# flute.net
KiCad netlist of a schematic drawn in EAGLE
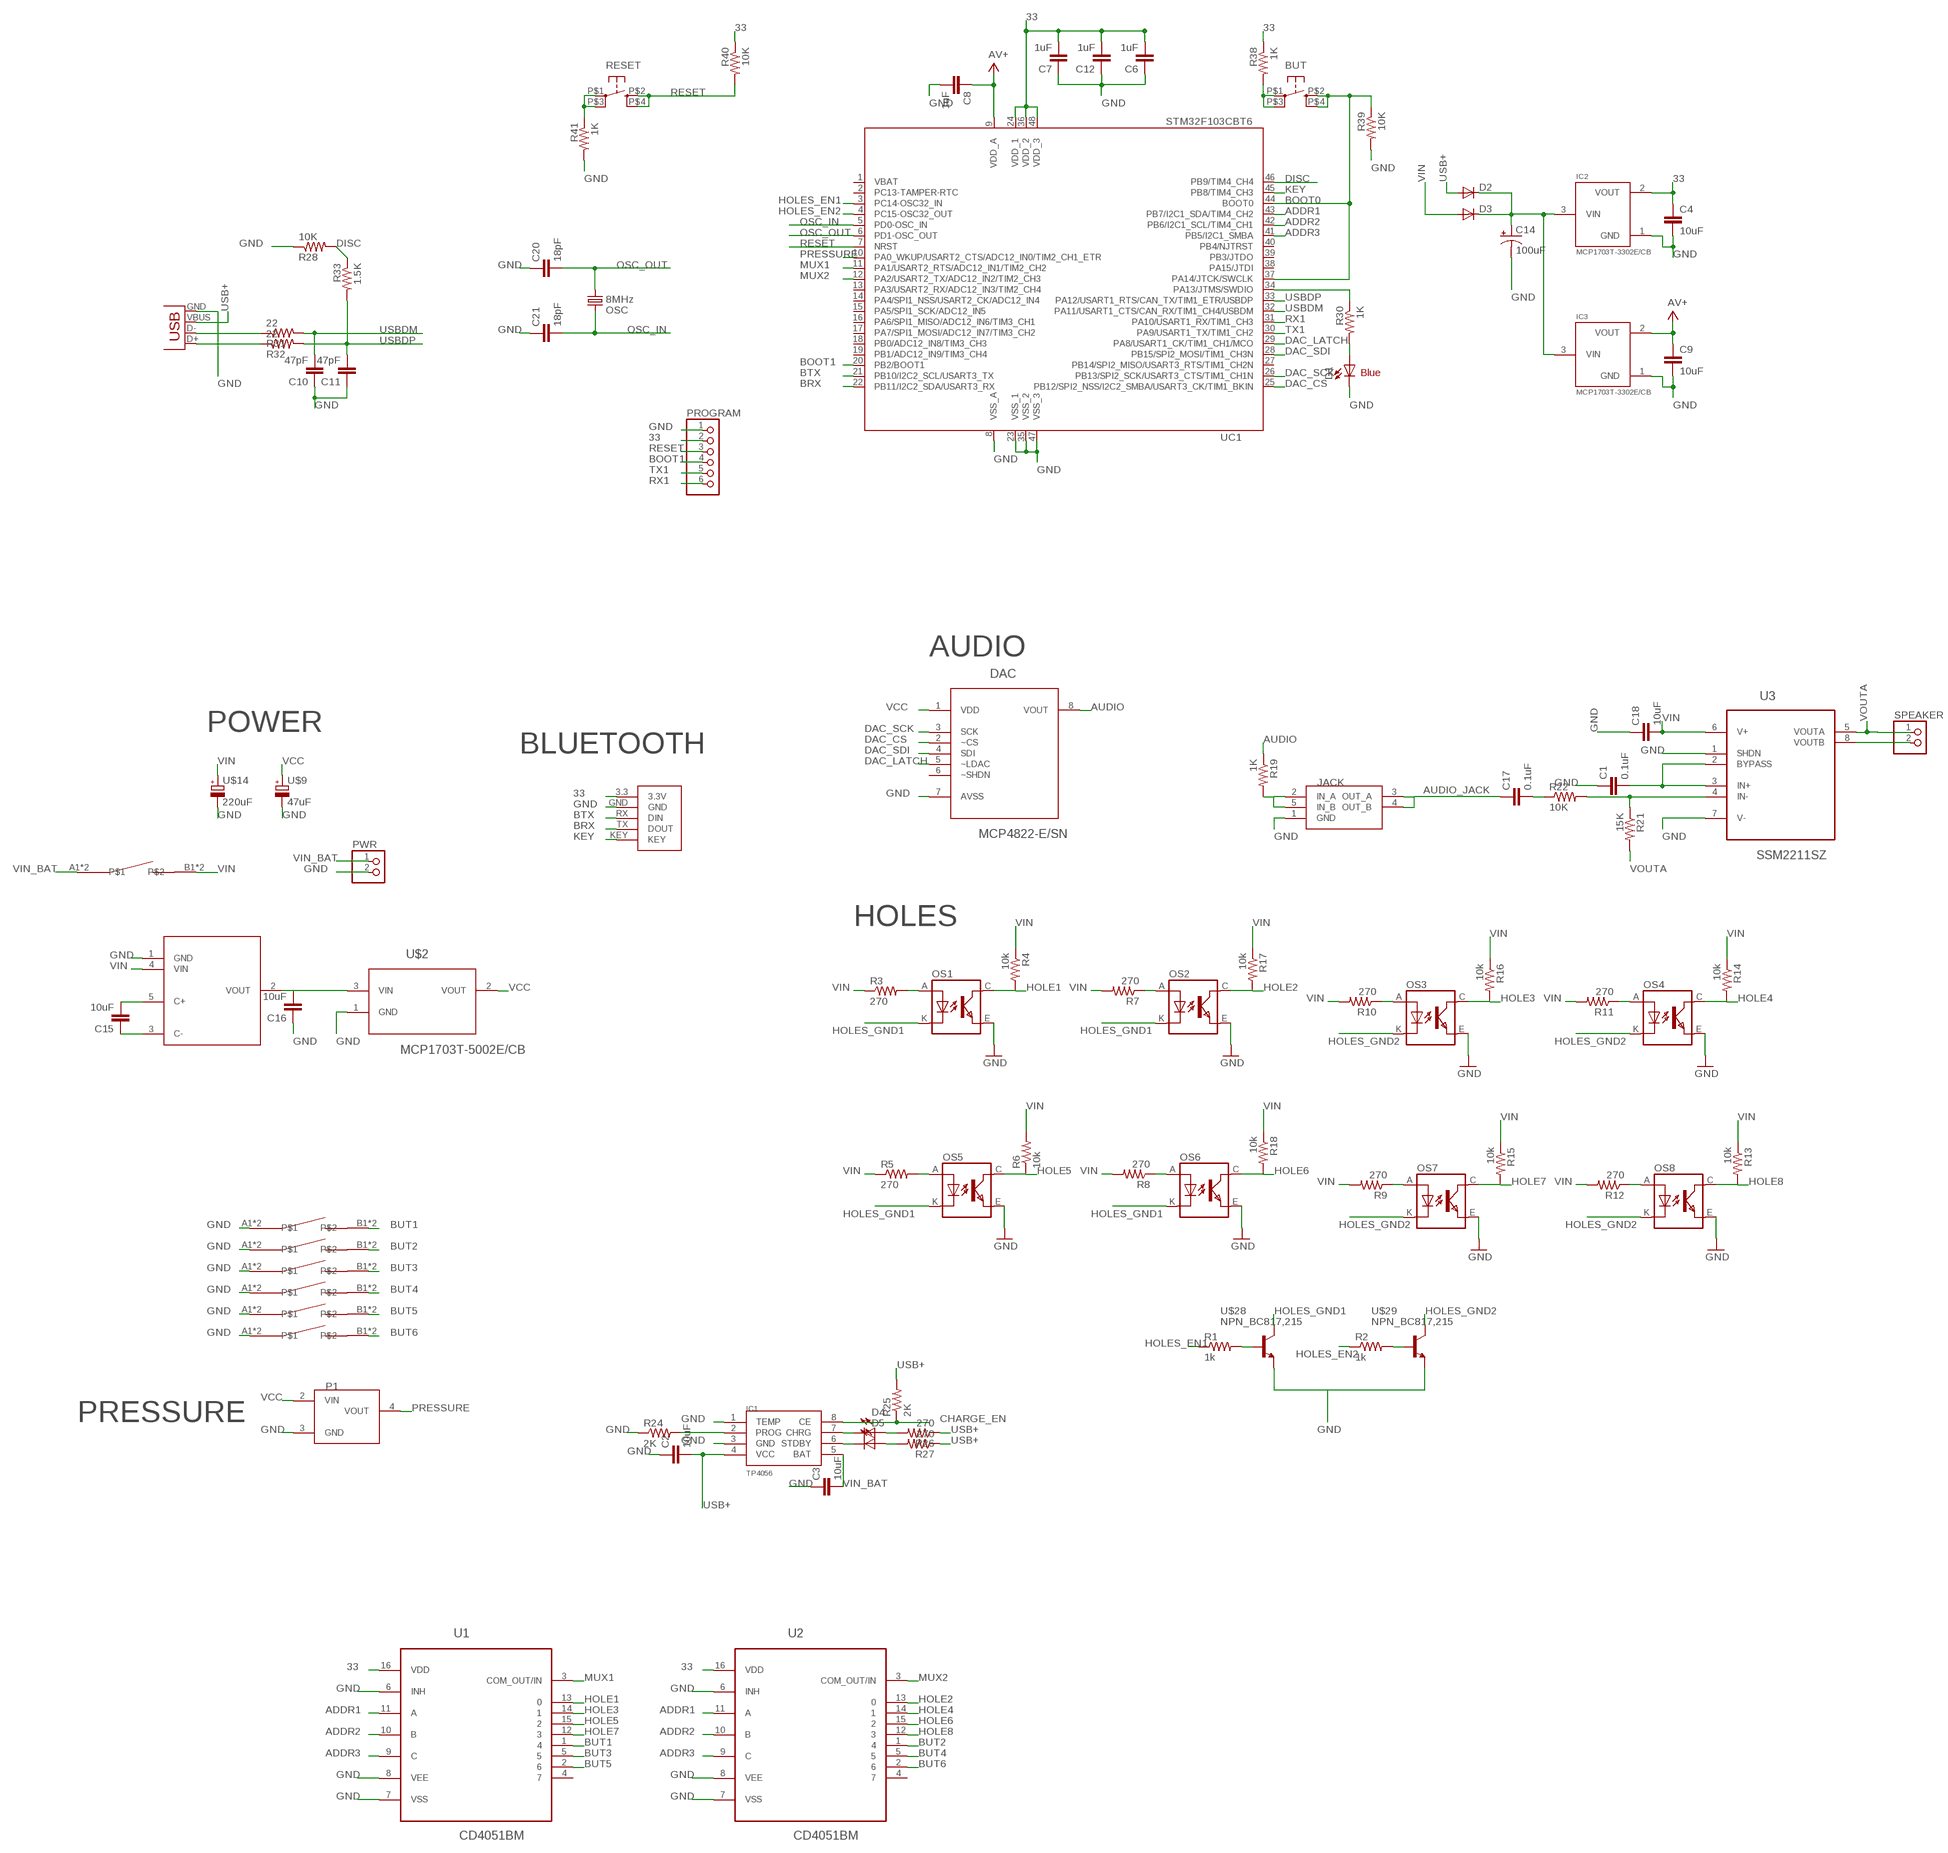
[diagram p0: schematic, sheet 1]

(export (version "E")
  (design (tool "Eeschema 10.0.6"))
  (components
    (comp (ref "BUT")
      (value "KMR211GLFS")
      (footprint "eagle-import:PUSHBUTTON-KMR241GLFS")
      (libsource (lib "eagle-import") (part "BUTTON-KMR241GLFS"))
    )
    (comp (ref "C1")
      (value "0.1uF")
      (footprint "eagle-import:0805")
      (libsource (lib "eagle-import") (part "CAP0805"))
    )
    (comp (ref "C2")
      (value "10uF")
      (footprint "eagle-import:0805")
      (libsource (lib "eagle-import") (part "CAP0805"))
    )
    (comp (ref "C3")
      (value "10uF")
      (footprint "eagle-import:0805")
      (libsource (lib "eagle-import") (part "CAP0805"))
    )
    (comp (ref "C4")
      (value "10uF")
      (footprint "eagle-import:0805")
      (libsource (lib "eagle-import") (part "SparkFun2_CAP0805"))
    )
    (comp (ref "C6")
      (value "1uF")
      (footprint "eagle-import:0805")
      (libsource (lib "eagle-import") (part "CAP0805"))
    )
    (comp (ref "C7")
      (value "1uF")
      (footprint "eagle-import:0805")
      (libsource (lib "eagle-import") (part "CAP0805"))
    )
    (comp (ref "C8")
      (value "1uF")
      (footprint "eagle-import:0805")
      (libsource (lib "eagle-import") (part "CAP0805"))
    )
    (comp (ref "C9")
      (value "10uF")
      (footprint "eagle-import:0805")
      (libsource (lib "eagle-import") (part "SparkFun2_CAP0805"))
    )
    (comp (ref "C10")
      (value "47pF")
      (footprint "eagle-import:0805")
      (libsource (lib "eagle-import") (part "CAP0805"))
    )
    (comp (ref "C11")
      (value "47pF")
      (footprint "eagle-import:0805")
      (libsource (lib "eagle-import") (part "CAP0805"))
    )
    (comp (ref "C12")
      (value "1uF")
      (footprint "eagle-import:0805")
      (libsource (lib "eagle-import") (part "CAP0805"))
    )
    (comp (ref "C14")
      (value "100uF")
      (footprint "eagle-import:EIA3216")
      (libsource (lib "eagle-import") (part "CAP_POL1206"))
    )
    (comp (ref "C15")
      (value "10uF")
      (footprint "eagle-import:0805")
      (libsource (lib "eagle-import") (part "CAP0805"))
    )
    (comp (ref "C16")
      (value "10uF")
      (footprint "eagle-import:0805")
      (libsource (lib "eagle-import") (part "CAP0805"))
    )
    (comp (ref "C17")
      (value "0.1uF")
      (footprint "eagle-import:0805")
      (libsource (lib "eagle-import") (part "CAP0805"))
    )
    (comp (ref "C18")
      (value "10uF")
      (footprint "eagle-import:0805")
      (libsource (lib "eagle-import") (part "CAP0805"))
    )
    (comp (ref "C20")
      (value "18pF")
      (footprint "eagle-import:0805")
      (libsource (lib "eagle-import") (part "CAP0805"))
    )
    (comp (ref "C21")
      (value "18pF")
      (footprint "eagle-import:0805")
      (libsource (lib "eagle-import") (part "CAP0805"))
    )
    (comp (ref "D1")
      (value "Blue")
      (footprint "eagle-import:LED-1206")
      (libsource (lib "eagle-import") (part "LED1206"))
    )
    (comp (ref "D2")
      (value "DIODESOD")
      (footprint "eagle-import:SOD-323")
      (libsource (lib "eagle-import") (part "DIODESOD"))
    )
    (comp (ref "D3")
      (value "DIODESOD")
      (footprint "eagle-import:SOD-323")
      (libsource (lib "eagle-import") (part "DIODESOD"))
    )
    (comp (ref "D4")
      (value "Red")
      (footprint "eagle-import:LED-1206")
      (libsource (lib "eagle-import") (part "LED1206"))
    )
    (comp (ref "D5")
      (value "Green")
      (footprint "eagle-import:LED-1206")
      (libsource (lib "eagle-import") (part "LED1206"))
    )
    (comp (ref "DAC")
      (value "MCP4822-E/SN")
      (footprint "eagle-import:SOIC8-N_MC")
      (libsource (lib "eagle-import") (part "MCP4822-E/SN"))
    )
    (comp (ref "IC1")
      (value "TP4056")
      (footprint "eagle-import:SOP-8")
      (libsource (lib "eagle-import") (part "TP4056"))
    )
    (comp (ref "IC2")
      (value "MCP1703T-3302E/CB")
      (footprint "eagle-import:SOT23")
      (libsource (lib "eagle-import") (part "MCP1700T"))
    )
    (comp (ref "IC3")
      (value "MCP1703T-3302E/CB")
      (footprint "eagle-import:SOT23")
      (libsource (lib "eagle-import") (part "MCP1700T"))
    )
    (comp (ref "JACK")
      (value "JACK")
      (footprint "eagle-import:3F07")
      (libsource (lib "eagle-import") (part "JACK"))
    )
    (comp (ref "OS1")
      (value "TCRT5000")
      (footprint "eagle-import:TCRT5000")
      (libsource (lib "eagle-import") (part "TCRT5000"))
    )
    (comp (ref "OS2")
      (value "TCRT5000")
      (footprint "eagle-import:TCRT5000")
      (libsource (lib "eagle-import") (part "TCRT5000"))
    )
    (comp (ref "OS3")
      (value "TCRT5000")
      (footprint "eagle-import:TCRT5000")
      (libsource (lib "eagle-import") (part "TCRT5000"))
    )
    (comp (ref "OS4")
      (value "TCRT5000")
      (footprint "eagle-import:TCRT5000")
      (libsource (lib "eagle-import") (part "TCRT5000"))
    )
    (comp (ref "OS5")
      (value "TCRT5000")
      (footprint "eagle-import:TCRT5000")
      (libsource (lib "eagle-import") (part "TCRT5000"))
    )
    (comp (ref "OS6")
      (value "TCRT5000")
      (footprint "eagle-import:TCRT5000")
      (libsource (lib "eagle-import") (part "TCRT5000"))
    )
    (comp (ref "OS7")
      (value "TCRT5000")
      (footprint "eagle-import:TCRT5000")
      (libsource (lib "eagle-import") (part "TCRT5000"))
    )
    (comp (ref "OS8")
      (value "TCRT5000")
      (footprint "eagle-import:TCRT5000")
      (libsource (lib "eagle-import") (part "TCRT5000"))
    )
    (comp (ref "OSC")
      (value "8MHz")
      (footprint "eagle-import:CRYSTAL-SMD-5X3")
      (libsource (lib "eagle-import") (part "CRYSTAL5X3"))
    )
    (comp (ref "P1")
      (value "PRESSURE_SENSOR")
      (footprint "eagle-import:MPXV5050GP")
      (libsource (lib "eagle-import") (part "PRESSURE_SENSOR"))
    )
    (comp (ref "PROGRAM")
      (value "CONNEC_1X066PADS")
      (footprint "eagle-import:6PADS")
      (libsource (lib "eagle-import") (part "CONNEC_1X066PADS"))
    )
    (comp (ref "PWR")
      (value "CONNEC_1X02BASIC")
      (footprint "eagle-import:CONNEC_1X02")
      (libsource (lib "eagle-import") (part "CONNEC_1X02BASIC"))
    )
    (comp (ref "R1")
      (value "1k")
      (footprint "eagle-import:0805")
      (libsource (lib "eagle-import") (part "RESISTOR0805-RES"))
    )
    (comp (ref "R2")
      (value "1k")
      (footprint "eagle-import:0805")
      (libsource (lib "eagle-import") (part "RESISTOR0805-RES"))
    )
    (comp (ref "R3")
      (value "270")
      (footprint "eagle-import:0805")
      (libsource (lib "eagle-import") (part "RESISTOR0805-RES"))
    )
    (comp (ref "R4")
      (value "10k")
      (footprint "eagle-import:0805")
      (libsource (lib "eagle-import") (part "RESISTOR0805-RES"))
    )
    (comp (ref "R5")
      (value "270")
      (footprint "eagle-import:0805")
      (libsource (lib "eagle-import") (part "RESISTOR0805-RES"))
    )
    (comp (ref "R6")
      (value "10k")
      (footprint "eagle-import:0805")
      (libsource (lib "eagle-import") (part "RESISTOR0805-RES"))
    )
    (comp (ref "R7")
      (value "270")
      (footprint "eagle-import:0805")
      (libsource (lib "eagle-import") (part "RESISTOR0805-RES"))
    )
    (comp (ref "R8")
      (value "270")
      (footprint "eagle-import:0805")
      (libsource (lib "eagle-import") (part "RESISTOR0805-RES"))
    )
    (comp (ref "R9")
      (value "270")
      (footprint "eagle-import:0805")
      (libsource (lib "eagle-import") (part "RESISTOR0805-RES"))
    )
    (comp (ref "R10")
      (value "270")
      (footprint "eagle-import:0805")
      (libsource (lib "eagle-import") (part "RESISTOR0805-RES"))
    )
    (comp (ref "R11")
      (value "270")
      (footprint "eagle-import:0805")
      (libsource (lib "eagle-import") (part "RESISTOR0805-RES"))
    )
    (comp (ref "R12")
      (value "270")
      (footprint "eagle-import:0805")
      (libsource (lib "eagle-import") (part "RESISTOR0805-RES"))
    )
    (comp (ref "R13")
      (value "10k")
      (footprint "eagle-import:0805")
      (libsource (lib "eagle-import") (part "RESISTOR0805-RES"))
    )
    (comp (ref "R14")
      (value "10k")
      (footprint "eagle-import:0805")
      (libsource (lib "eagle-import") (part "RESISTOR0805-RES"))
    )
    (comp (ref "R15")
      (value "10k")
      (footprint "eagle-import:0805")
      (libsource (lib "eagle-import") (part "RESISTOR0805-RES"))
    )
    (comp (ref "R16")
      (value "10k")
      (footprint "eagle-import:0805")
      (libsource (lib "eagle-import") (part "RESISTOR0805-RES"))
    )
    (comp (ref "R17")
      (value "10k")
      (footprint "eagle-import:0805")
      (libsource (lib "eagle-import") (part "RESISTOR0805-RES"))
    )
    (comp (ref "R18")
      (value "10k")
      (footprint "eagle-import:0805")
      (libsource (lib "eagle-import") (part "RESISTOR0805-RES"))
    )
    (comp (ref "R19")
      (value "1K")
      (footprint "eagle-import:0805")
      (libsource (lib "eagle-import") (part "RESISTOR0805-RES"))
    )
    (comp (ref "R21")
      (value "15K")
      (footprint "eagle-import:0805")
      (libsource (lib "eagle-import") (part "RESISTOR0805-RES"))
    )
    (comp (ref "R22")
      (value "10K")
      (footprint "eagle-import:0805")
      (libsource (lib "eagle-import") (part "RESISTOR0805-RES"))
    )
    (comp (ref "R24")
      (value "2K")
      (footprint "eagle-import:0805")
      (libsource (lib "eagle-import") (part "RESISTOR0805-RES"))
    )
    (comp (ref "R25")
      (value "2K")
      (footprint "eagle-import:0805")
      (libsource (lib "eagle-import") (part "RESISTOR0805-RES"))
    )
    (comp (ref "R26")
      (value "270")
      (footprint "eagle-import:0805")
      (libsource (lib "eagle-import") (part "RESISTOR0805-RES"))
    )
    (comp (ref "R27")
      (value "270")
      (footprint "eagle-import:0805")
      (libsource (lib "eagle-import") (part "RESISTOR0805-RES"))
    )
    (comp (ref "R28")
      (value "10K")
      (footprint "eagle-import:0805")
      (libsource (lib "eagle-import") (part "RESISTOR0805-RES"))
    )
    (comp (ref "R30")
      (value "1K")
      (footprint "eagle-import:0805")
      (libsource (lib "eagle-import") (part "RESISTOR0805-RES"))
    )
    (comp (ref "R31")
      (value "22")
      (footprint "eagle-import:0805")
      (libsource (lib "eagle-import") (part "RESISTOR0805-RES"))
    )
    (comp (ref "R32")
      (value "22")
      (footprint "eagle-import:0805")
      (libsource (lib "eagle-import") (part "RESISTOR0805-RES"))
    )
    (comp (ref "R33")
      (value "1.5K")
      (footprint "eagle-import:0805")
      (libsource (lib "eagle-import") (part "RESISTOR0805-RES"))
    )
    (comp (ref "R38")
      (value "1K")
      (footprint "eagle-import:0805")
      (libsource (lib "eagle-import") (part "RESISTOR0805-RES"))
    )
    (comp (ref "R39")
      (value "10K")
      (footprint "eagle-import:0805")
      (libsource (lib "eagle-import") (part "RESISTOR0805-RES"))
    )
    (comp (ref "R40")
      (value "10K")
      (footprint "eagle-import:0805")
      (libsource (lib "eagle-import") (part "RESISTOR0805-RES"))
    )
    (comp (ref "R41")
      (value "1K")
      (footprint "eagle-import:0805")
      (libsource (lib "eagle-import") (part "RESISTOR0805-RES"))
    )
    (comp (ref "RESET")
      (value "KMR211GLFS")
      (footprint "eagle-import:PUSHBUTTON-KMR241GLFS")
      (libsource (lib "eagle-import") (part "BUTTON-KMR241GLFS"))
    )
    (comp (ref "SPEAKER")
      (value "CONNEC_1X02BASIC")
      (footprint "eagle-import:CONNEC_1X02")
      (libsource (lib "eagle-import") (part "CONNEC_1X02BASIC"))
    )
    (comp (ref "U$1")
      (value "MAX1683")
      (footprint "eagle-import:SOT23-5")
      (libsource (lib "eagle-import") (part "MAX1683"))
    )
    (comp (ref "U$2")
      (value "MCP1703T-5002E/CB")
      (footprint "eagle-import:SOT95P300X145-3N")
      (libsource (lib "eagle-import") (part "MCP1703T-5002E/CB"))
    )
    (comp (ref "U$9")
      (value "47uF")
      (footprint "eagle-import:PANASONIC_D")
      (libsource (lib "eagle-import") (part "CPOL_EUPANASONIC_D"))
    )
    (comp (ref "U$14")
      (value "220uF")
      (footprint "eagle-import:PANASONIC_D8")
      (libsource (lib "eagle-import") (part "CPOL_EUPANASONIC_D8"))
    )
    (comp (ref "U$16")
      (value "SWITCHKCD11")
      (footprint "eagle-import:KCD11")
      (libsource (lib "eagle-import") (part "SWITCHKCD11"))
    )
    (comp (ref "U$18")
      (value "SWITCH6X6X10")
      (footprint "eagle-import:SWITCH_6X6X10")
      (libsource (lib "eagle-import") (part "SWITCH6X6X10"))
    )
    (comp (ref "U$19")
      (value "SWITCH6X6X10")
      (footprint "eagle-import:SWITCH_6X6X10")
      (libsource (lib "eagle-import") (part "SWITCH6X6X10"))
    )
    (comp (ref "U$20")
      (value "SWITCH6X6X10")
      (footprint "eagle-import:SWITCH_6X6X10")
      (libsource (lib "eagle-import") (part "SWITCH6X6X10"))
    )
    (comp (ref "U$21")
      (value "SWITCH6X6X10")
      (footprint "eagle-import:SWITCH_6X6X10")
      (libsource (lib "eagle-import") (part "SWITCH6X6X10"))
    )
    (comp (ref "U$22")
      (value "SWITCH6X6X10")
      (footprint "eagle-import:SWITCH_6X6X10")
      (libsource (lib "eagle-import") (part "SWITCH6X6X10"))
    )
    (comp (ref "U$23")
      (value "SWITCH6X6X10")
      (footprint "eagle-import:SWITCH_6X6X10")
      (libsource (lib "eagle-import") (part "SWITCH6X6X10"))
    )
    (comp (ref "U$24")
      (value "HC05")
      (footprint "eagle-import:HC-05")
      (libsource (lib "eagle-import") (part "HC05"))
    )
    (comp (ref "U$28")
      (value "NPN_BC817,215")
      (footprint "eagle-import:SOT-23")
      (libsource (lib "eagle-import") (part "NPN_BC817,215"))
    )
    (comp (ref "U$29")
      (value "NPN_BC817,215")
      (footprint "eagle-import:SOT-23")
      (libsource (lib "eagle-import") (part "NPN_BC817,215"))
    )
    (comp (ref "U1")
      (value "CD4051BM")
      (footprint "eagle-import:SOIC127P600X175-16N")
      (libsource (lib "eagle-import") (part "CD4051BM"))
    )
    (comp (ref "U2")
      (value "CD4051BM")
      (footprint "eagle-import:SOIC127P600X175-16N")
      (libsource (lib "eagle-import") (part "CD4051BM"))
    )
    (comp (ref "U3")
      (value "SSM2211SZ")
      (footprint "eagle-import:SOIC127P600X175-8N")
      (libsource (lib "eagle-import") (part "SSM2211SZ"))
    )
    (comp (ref "UC1")
      (value "STM32F103CBT6")
      (footprint "eagle-import:LQFP48")
      (libsource (lib "eagle-import") (part "STM32F103CB"))
    )
    (comp (ref "X1")
      (value "USB-MINIB")
      (footprint "eagle-import:USB-MINIB")
      (libsource (lib "eagle-import") (part "USBSMD"))
    )
  )
  (nets
    (net (code "1") (name "/33") (class "Default")
      (node (ref "C12") (pin "2") (pinfunction "2_2") (pintype "passive"))
      (node (ref "C4") (pin "1") (pinfunction "1_1") (pintype "passive"))
      (node (ref "C6") (pin "2") (pinfunction "2_2") (pintype "passive"))
      (node (ref "C7") (pin "2") (pinfunction "2_2") (pintype "passive"))
      (node (ref "IC2") (pin "2") (pinfunction "VOUT_2") (pintype "bidirectional"))
      (node (ref "PROGRAM") (pin "2") (pinfunction "2_2") (pintype "passive"))
      (node (ref "R38") (pin "1") (pinfunction "1_1") (pintype "passive"))
      (node (ref "R40") (pin "1") (pinfunction "1_1") (pintype "passive"))
      (node (ref "U$24") (pin "3.3") (pinfunction "3.3V_3.3") (pintype "bidirectional"))
      (node (ref "U1") (pin "16") (pinfunction "VDD_16") (pintype "input"))
      (node (ref "U2") (pin "16") (pinfunction "VDD_16") (pintype "input"))
      (node (ref "UC1") (pin "24") (pinfunction "VDD_1_24") (pintype "power_in"))
      (node (ref "UC1") (pin "36") (pinfunction "VDD_2_36") (pintype "power_in"))
      (node (ref "UC1") (pin "48") (pinfunction "VDD_3_48") (pintype "power_in"))
    )
    (net (code "2") (name "/ADDR1") (class "Default")
      (node (ref "U1") (pin "11") (pinfunction "A_11") (pintype "input"))
      (node (ref "U2") (pin "11") (pinfunction "A_11") (pintype "input"))
      (node (ref "UC1") (pin "43") (pinfunction "PB7/I2C1_SDA/TIM4_CH2_43") (pintype "bidirectional"))
    )
    (net (code "3") (name "/ADDR2") (class "Default")
      (node (ref "U1") (pin "10") (pinfunction "B_10") (pintype "input"))
      (node (ref "U2") (pin "10") (pinfunction "B_10") (pintype "input"))
      (node (ref "UC1") (pin "42") (pinfunction "PB6/I2C1_SCL/TIM4_CH1_42") (pintype "input"))
    )
    (net (code "4") (name "/ADDR3") (class "Default")
      (node (ref "U1") (pin "9") (pinfunction "C_9") (pintype "bidirectional"))
      (node (ref "U2") (pin "9") (pinfunction "C_9") (pintype "bidirectional"))
      (node (ref "UC1") (pin "41") (pinfunction "PB5/I2C1_SMBA_41") (pintype "input"))
    )
    (net (code "5") (name "/AUDIO") (class "Default")
      (node (ref "DAC") (pin "8") (pinfunction "VOUT_8") (pintype "output"))
      (node (ref "R19") (pin "1") (pinfunction "1_1") (pintype "passive"))
    )
    (net (code "6") (name "/AUDIO_JACK") (class "Default")
      (node (ref "C17") (pin "1") (pinfunction "1_1") (pintype "passive"))
      (node (ref "JACK") (pin "3") (pinfunction "OUT_A_3") (pintype "bidirectional"))
      (node (ref "JACK") (pin "4") (pinfunction "OUT_B_4") (pintype "bidirectional"))
    )
    (net (code "7") (name "/BOOT1") (class "Default")
      (node (ref "PROGRAM") (pin "4") (pinfunction "4_4") (pintype "passive"))
      (node (ref "UC1") (pin "20") (pinfunction "PB2/BOOT1_20") (pintype "bidirectional"))
    )
    (net (code "8") (name "/BRX") (class "Default")
      (node (ref "U$24") (pin "TX") (pinfunction "DOUT_TX") (pintype "bidirectional"))
      (node (ref "UC1") (pin "22") (pinfunction "PB11/I2C2_SDA/USART3_RX_22") (pintype "input"))
    )
    (net (code "9") (name "/BTX") (class "Default")
      (node (ref "U$24") (pin "RX") (pinfunction "DIN_RX") (pintype "bidirectional"))
      (node (ref "UC1") (pin "21") (pinfunction "PB10/I2C2_SCL/USART3_TX_21") (pintype "input"))
    )
    (net (code "10") (name "/BUT1") (class "Default")
      (node (ref "U$18") (pin "B1") (pinfunction "P$2_B1") (pintype "bidirectional"))
      (node (ref "U$18") (pin "B2") (pinfunction "P$2_B2") (pintype "bidirectional"))
      (node (ref "U1") (pin "1") (pinfunction "4_1") (pintype "bidirectional"))
    )
    (net (code "11") (name "/BUT2") (class "Default")
      (node (ref "U$19") (pin "B1") (pinfunction "P$2_B1") (pintype "bidirectional"))
      (node (ref "U$19") (pin "B2") (pinfunction "P$2_B2") (pintype "bidirectional"))
      (node (ref "U2") (pin "1") (pinfunction "4_1") (pintype "bidirectional"))
    )
    (net (code "12") (name "/BUT3") (class "Default")
      (node (ref "U$20") (pin "B1") (pinfunction "P$2_B1") (pintype "bidirectional"))
      (node (ref "U$20") (pin "B2") (pinfunction "P$2_B2") (pintype "bidirectional"))
      (node (ref "U1") (pin "5") (pinfunction "5_5") (pintype "bidirectional"))
    )
    (net (code "13") (name "/BUT4") (class "Default")
      (node (ref "U$21") (pin "B1") (pinfunction "P$2_B1") (pintype "bidirectional"))
      (node (ref "U$21") (pin "B2") (pinfunction "P$2_B2") (pintype "bidirectional"))
      (node (ref "U2") (pin "5") (pinfunction "5_5") (pintype "bidirectional"))
    )
    (net (code "14") (name "/BUT5") (class "Default")
      (node (ref "U$22") (pin "B1") (pinfunction "P$2_B1") (pintype "bidirectional"))
      (node (ref "U$22") (pin "B2") (pinfunction "P$2_B2") (pintype "bidirectional"))
      (node (ref "U1") (pin "2") (pinfunction "6_2") (pintype "bidirectional"))
    )
    (net (code "15") (name "/BUT6") (class "Default")
      (node (ref "U$23") (pin "B1") (pinfunction "P$2_B1") (pintype "bidirectional"))
      (node (ref "U$23") (pin "B2") (pinfunction "P$2_B2") (pintype "bidirectional"))
      (node (ref "U2") (pin "2") (pinfunction "6_2") (pintype "bidirectional"))
    )
    (net (code "16") (name "/CHARGE_EN") (class "Default")
      (node (ref "IC1") (pin "8") (pinfunction "CE_8") (pintype "bidirectional"))
      (node (ref "R25") (pin "1") (pinfunction "1_1") (pintype "passive"))
    )
    (net (code "17") (name "/DAC_CS") (class "Default")
      (node (ref "DAC") (pin "2") (pinfunction "~{CS}_2") (pintype "input"))
      (node (ref "UC1") (pin "25") (pinfunction "PB12/SPI2_NSS/I2C2_SMBA/USART3_CK/TIM1_BKIN_25") (pintype "input"))
    )
    (net (code "18") (name "/DAC_LATCH") (class "Default")
      (node (ref "DAC") (pin "5") (pinfunction "~{LDAC}_5") (pintype "input"))
      (node (ref "UC1") (pin "29") (pinfunction "PA8/USART1_CK/TIM1_CH1/MCO_29") (pintype "bidirectional"))
    )
    (net (code "19") (name "/DAC_SCK") (class "Default")
      (node (ref "DAC") (pin "3") (pinfunction "SCK_3") (pintype "input"))
      (node (ref "UC1") (pin "26") (pinfunction "PB13/SPI2_SCK/USART3_CTS/TIM1_CH1N_26") (pintype "input"))
    )
    (net (code "20") (name "/DAC_SDI") (class "Default")
      (node (ref "DAC") (pin "4") (pinfunction "SDI_4") (pintype "input"))
      (node (ref "UC1") (pin "28") (pinfunction "PB15/SPI2_MOSI/TIM1_CH3N_28") (pintype "input"))
    )
    (net (code "21") (name "/DISC") (class "Default")
      (node (ref "R28") (pin "2") (pinfunction "2_2") (pintype "passive"))
      (node (ref "R33") (pin "1") (pinfunction "1_1") (pintype "passive"))
      (node (ref "UC1") (pin "46") (pinfunction "PB9/TIM4_CH4_46") (pintype "input"))
    )
    (net (code "22") (name "/HOLE1") (class "Default")
      (node (ref "OS1") (pin "C") (pinfunction "COLLECTOR_C") (pintype "passive"))
      (node (ref "R4") (pin "2") (pinfunction "2_2") (pintype "passive"))
      (node (ref "U1") (pin "13") (pinfunction "0_13") (pintype "bidirectional"))
    )
    (net (code "23") (name "/HOLE2") (class "Default")
      (node (ref "OS2") (pin "C") (pinfunction "COLLECTOR_C") (pintype "passive"))
      (node (ref "R17") (pin "2") (pinfunction "2_2") (pintype "passive"))
      (node (ref "U2") (pin "13") (pinfunction "0_13") (pintype "bidirectional"))
    )
    (net (code "24") (name "/HOLE3") (class "Default")
      (node (ref "OS3") (pin "C") (pinfunction "COLLECTOR_C") (pintype "passive"))
      (node (ref "R16") (pin "2") (pinfunction "2_2") (pintype "passive"))
      (node (ref "U1") (pin "14") (pinfunction "1_14") (pintype "bidirectional"))
    )
    (net (code "25") (name "/HOLE4") (class "Default")
      (node (ref "OS4") (pin "C") (pinfunction "COLLECTOR_C") (pintype "passive"))
      (node (ref "R14") (pin "2") (pinfunction "2_2") (pintype "passive"))
      (node (ref "U2") (pin "14") (pinfunction "1_14") (pintype "bidirectional"))
    )
    (net (code "26") (name "/HOLE5") (class "Default")
      (node (ref "OS5") (pin "C") (pinfunction "COLLECTOR_C") (pintype "passive"))
      (node (ref "R6") (pin "1") (pinfunction "1_1") (pintype "passive"))
      (node (ref "U1") (pin "15") (pinfunction "2_15") (pintype "bidirectional"))
    )
    (net (code "27") (name "/HOLE6") (class "Default")
      (node (ref "OS6") (pin "C") (pinfunction "COLLECTOR_C") (pintype "passive"))
      (node (ref "R18") (pin "2") (pinfunction "2_2") (pintype "passive"))
      (node (ref "U2") (pin "15") (pinfunction "2_15") (pintype "bidirectional"))
    )
    (net (code "28") (name "/HOLE7") (class "Default")
      (node (ref "OS7") (pin "C") (pinfunction "COLLECTOR_C") (pintype "passive"))
      (node (ref "R15") (pin "2") (pinfunction "2_2") (pintype "passive"))
      (node (ref "U1") (pin "12") (pinfunction "3_12") (pintype "bidirectional"))
    )
    (net (code "29") (name "/HOLE8") (class "Default")
      (node (ref "OS8") (pin "C") (pinfunction "COLLECTOR_C") (pintype "passive"))
      (node (ref "R13") (pin "2") (pinfunction "2_2") (pintype "passive"))
      (node (ref "U2") (pin "12") (pinfunction "3_12") (pintype "bidirectional"))
    )
    (net (code "30") (name "/HOLES_EN1") (class "Default")
      (node (ref "R1") (pin "1") (pinfunction "1_1") (pintype "passive"))
      (node (ref "UC1") (pin "3") (pinfunction "PC14-OSC32_IN_3") (pintype "input"))
    )
    (net (code "31") (name "/HOLES_EN2") (class "Default")
      (node (ref "R2") (pin "1") (pinfunction "1_1") (pintype "passive"))
      (node (ref "UC1") (pin "4") (pinfunction "PC15-OSC32_OUT_4") (pintype "input"))
    )
    (net (code "32") (name "/HOLES_GND1") (class "Default")
      (node (ref "OS1") (pin "K") (pinfunction "CATHODE_K") (pintype "passive"))
      (node (ref "OS2") (pin "K") (pinfunction "CATHODE_K") (pintype "passive"))
      (node (ref "OS5") (pin "K") (pinfunction "CATHODE_K") (pintype "passive"))
      (node (ref "OS6") (pin "K") (pinfunction "CATHODE_K") (pintype "passive"))
      (node (ref "U$28") (pin "3") (pinfunction "C_3") (pintype "passive"))
    )
    (net (code "33") (name "/HOLES_GND2") (class "Default")
      (node (ref "OS3") (pin "K") (pinfunction "CATHODE_K") (pintype "passive"))
      (node (ref "OS4") (pin "K") (pinfunction "CATHODE_K") (pintype "passive"))
      (node (ref "OS7") (pin "K") (pinfunction "CATHODE_K") (pintype "passive"))
      (node (ref "OS8") (pin "K") (pinfunction "CATHODE_K") (pintype "passive"))
      (node (ref "U$29") (pin "3") (pinfunction "C_3") (pintype "passive"))
    )
    (net (code "34") (name "/KEY") (class "Default")
      (node (ref "U$24") (pin "KEY") (pinfunction "KEY_KEY") (pintype "bidirectional"))
      (node (ref "UC1") (pin "45") (pinfunction "PB8/TIM4_CH3_45") (pintype "bidirectional"))
    )
    (net (code "35") (name "/MUX1") (class "Default")
      (node (ref "U1") (pin "3") (pinfunction "COM_OUT/IN_3") (pintype "bidirectional"))
      (node (ref "UC1") (pin "11") (pinfunction "PA1/USART2_RTS/ADC12_IN1/TIM2_CH2_11") (pintype "bidirectional"))
    )
    (net (code "36") (name "/MUX2") (class "Default")
      (node (ref "U2") (pin "3") (pinfunction "COM_OUT/IN_3") (pintype "bidirectional"))
      (node (ref "UC1") (pin "12") (pinfunction "PA2/USART2_TX/ADC12_IN2/TIM2_CH3_12") (pintype "bidirectional"))
    )
    (net (code "37") (name "/OSC_IN") (class "Default")
      (node (ref "C21") (pin "2") (pinfunction "2_2") (pintype "passive"))
      (node (ref "OSC") (pin "3") (pinfunction "2_3") (pintype "passive"))
      (node (ref "UC1") (pin "5") (pinfunction "PD0-OSC_IN_5") (pintype "input"))
    )
    (net (code "38") (name "/OSC_OUT") (class "Default")
      (node (ref "C20") (pin "2") (pinfunction "2_2") (pintype "passive"))
      (node (ref "OSC") (pin "1") (pinfunction "1_1") (pintype "passive"))
      (node (ref "UC1") (pin "6") (pinfunction "PD1-OSC_OUT_6") (pintype "input"))
    )
    (net (code "39") (name "/PRESSURE") (class "Default")
      (node (ref "P1") (pin "4") (pinfunction "VOUT_4") (pintype "bidirectional"))
      (node (ref "UC1") (pin "10") (pinfunction "PA0_WKUP/USART2_CTS/ADC12_IN0/TIM2_CH1_ETR_10") (pintype "bidirectional"))
    )
    (net (code "40") (name "/RESET") (class "Default")
      (node (ref "PROGRAM") (pin "3") (pinfunction "3_3") (pintype "passive"))
      (node (ref "R40") (pin "2") (pinfunction "2_2") (pintype "passive"))
      (node (ref "RESET") (pin "P$2") (pinfunction "2_P$2") (pintype "passive"))
      (node (ref "RESET") (pin "P$4") (pinfunction "4_P$4") (pintype "passive"))
      (node (ref "UC1") (pin "7") (pinfunction "NRST_7") (pintype "input"))
    )
    (net (code "41") (name "/RX1") (class "Default")
      (node (ref "PROGRAM") (pin "6") (pinfunction "6_6") (pintype "passive"))
      (node (ref "UC1") (pin "31") (pinfunction "PA10/USART1_RX/TIM1_CH3_31") (pintype "bidirectional"))
    )
    (net (code "42") (name "/TX1") (class "Default")
      (node (ref "PROGRAM") (pin "5") (pinfunction "5_5") (pintype "passive"))
      (node (ref "UC1") (pin "30") (pinfunction "PA9/USART1_TX/TIM1_CH2_30") (pintype "input"))
    )
    (net (code "43") (name "/USB+") (class "Default")
      (node (ref "C2") (pin "2") (pinfunction "2_2") (pintype "passive"))
      (node (ref "D2") (pin "2") (pinfunction "A_2") (pintype "passive"))
      (node (ref "IC1") (pin "4") (pinfunction "VCC_4") (pintype "bidirectional"))
      (node (ref "R25") (pin "2") (pinfunction "2_2") (pintype "passive"))
      (node (ref "R26") (pin "1") (pinfunction "1_1") (pintype "passive"))
      (node (ref "R27") (pin "1") (pinfunction "1_1") (pintype "passive"))
      (node (ref "X1") (pin "VBUS") (pinfunction "VBUS_VBUS") (pintype "bidirectional"))
    )
    (net (code "44") (name "/USBDM") (class "Default")
      (node (ref "C10") (pin "2") (pinfunction "2_2") (pintype "passive"))
      (node (ref "R31") (pin "2") (pinfunction "2_2") (pintype "passive"))
      (node (ref "UC1") (pin "32") (pinfunction "PA11/USART1_CTS/CAN_RX/TIM1_CH4/USBDM_32") (pintype "bidirectional"))
    )
    (net (code "45") (name "/USBDP") (class "Default")
      (node (ref "C11") (pin "2") (pinfunction "2_2") (pintype "passive"))
      (node (ref "R32") (pin "2") (pinfunction "2_2") (pintype "passive"))
      (node (ref "R33") (pin "2") (pinfunction "2_2") (pintype "passive"))
      (node (ref "UC1") (pin "33") (pinfunction "PA12/USART1_RTS/CAN_TX/TIM1_ETR/USBDP_33") (pintype "bidirectional"))
    )
    (net (code "46") (name "/VBAT") (class "Default")
      (node (ref "UC1") (pin "1") (pinfunction "VBAT_1") (pintype "power_in"))
    )
    (net (code "47") (name "/VCC") (class "Default")
      (node (ref "DAC") (pin "1") (pinfunction "VDD_1") (pintype "power_in"))
      (node (ref "P1") (pin "2") (pinfunction "VIN_2") (pintype "bidirectional"))
      (node (ref "U$2") (pin "2") (pinfunction "VOUT_2") (pintype "output"))
      (node (ref "U$9") (pin "+") (pinfunction "+_+") (pintype "passive"))
    )
    (net (code "48") (name "/VIN") (class "Default")
      (node (ref "C18") (pin "2") (pinfunction "2_2") (pintype "passive"))
      (node (ref "D3") (pin "2") (pinfunction "A_2") (pintype "passive"))
      (node (ref "R10") (pin "2") (pinfunction "2_2") (pintype "passive"))
      (node (ref "R11") (pin "2") (pinfunction "2_2") (pintype "passive"))
      (node (ref "R12") (pin "2") (pinfunction "2_2") (pintype "passive"))
      (node (ref "R13") (pin "1") (pinfunction "1_1") (pintype "passive"))
      (node (ref "R14") (pin "1") (pinfunction "1_1") (pintype "passive"))
      (node (ref "R15") (pin "1") (pinfunction "1_1") (pintype "passive"))
      (node (ref "R16") (pin "1") (pinfunction "1_1") (pintype "passive"))
      (node (ref "R17") (pin "1") (pinfunction "1_1") (pintype "passive"))
      (node (ref "R18") (pin "1") (pinfunction "1_1") (pintype "passive"))
      (node (ref "R3") (pin "1") (pinfunction "1_1") (pintype "passive"))
      (node (ref "R4") (pin "1") (pinfunction "1_1") (pintype "passive"))
      (node (ref "R5") (pin "1") (pinfunction "1_1") (pintype "passive"))
      (node (ref "R6") (pin "2") (pinfunction "2_2") (pintype "passive"))
      (node (ref "R7") (pin "2") (pinfunction "2_2") (pintype "passive"))
      (node (ref "R8") (pin "2") (pinfunction "2_2") (pintype "passive"))
      (node (ref "R9") (pin "2") (pinfunction "2_2") (pintype "passive"))
      (node (ref "U$1") (pin "4") (pinfunction "VIN_4") (pintype "bidirectional"))
      (node (ref "U$14") (pin "+") (pinfunction "+_+") (pintype "passive"))
      (node (ref "U$16") (pin "B1") (pinfunction "P$2_B1") (pintype "bidirectional"))
      (node (ref "U$16") (pin "B2") (pinfunction "P$2_B2") (pintype "bidirectional"))
      (node (ref "U3") (pin "6") (pinfunction "V+_6") (pintype "power_in"))
    )
    (net (code "49") (name "/VIN_BAT") (class "Default")
      (node (ref "C3") (pin "2") (pinfunction "2_2") (pintype "passive"))
      (node (ref "IC1") (pin "5") (pinfunction "BAT_5") (pintype "bidirectional"))
      (node (ref "PWR") (pin "1") (pinfunction "1_1") (pintype "passive"))
      (node (ref "U$16") (pin "A1") (pinfunction "P$1_A1") (pintype "bidirectional"))
      (node (ref "U$16") (pin "A2") (pinfunction "P$1_A2") (pintype "bidirectional"))
    )
    (net (code "50") (name "/VOUTA") (class "Default")
      (node (ref "R21") (pin "2") (pinfunction "2_2") (pintype "passive"))
      (node (ref "SPEAKER") (pin "1") (pinfunction "1_1") (pintype "passive"))
      (node (ref "U3") (pin "5") (pinfunction "VOUTA_5") (pintype "output"))
    )
    (net (code "51") (name "AV+") (class "Default")
      (node (ref "C8") (pin "1") (pinfunction "1_1") (pintype "passive"))
      (node (ref "C9") (pin "1") (pinfunction "1_1") (pintype "passive"))
      (node (ref "IC3") (pin "2") (pinfunction "VOUT_2") (pintype "bidirectional"))
      (node (ref "UC1") (pin "9") (pinfunction "VDD_A_9") (pintype "power_in"))
    )
    (net (code "52") (name "GND") (class "Default")
      (node (ref "C1") (pin "1") (pinfunction "1_1") (pintype "passive"))
      (node (ref "C10") (pin "1") (pinfunction "1_1") (pintype "passive"))
      (node (ref "C11") (pin "1") (pinfunction "1_1") (pintype "passive"))
      (node (ref "C12") (pin "1") (pinfunction "1_1") (pintype "passive"))
      (node (ref "C14") (pin "C") (pinfunction "-_C") (pintype "passive"))
      (node (ref "C16") (pin "1") (pinfunction "1_1") (pintype "passive"))
      (node (ref "C18") (pin "1") (pinfunction "1_1") (pintype "passive"))
      (node (ref "C2") (pin "1") (pinfunction "1_1") (pintype "passive"))
      (node (ref "C20") (pin "1") (pinfunction "1_1") (pintype "passive"))
      (node (ref "C21") (pin "1") (pinfunction "1_1") (pintype "passive"))
      (node (ref "C3") (pin "1") (pinfunction "1_1") (pintype "passive"))
      (node (ref "C4") (pin "2") (pinfunction "2_2") (pintype "passive"))
      (node (ref "C6") (pin "1") (pinfunction "1_1") (pintype "passive"))
      (node (ref "C7") (pin "1") (pinfunction "1_1") (pintype "passive"))
      (node (ref "C8") (pin "2") (pinfunction "2_2") (pintype "passive"))
      (node (ref "C9") (pin "2") (pinfunction "2_2") (pintype "passive"))
      (node (ref "D1") (pin "C") (pinfunction "C_C") (pintype "passive"))
      (node (ref "DAC") (pin "7") (pinfunction "AVSS_7") (pintype "power_in"))
      (node (ref "IC1") (pin "1") (pinfunction "TEMP_1") (pintype "bidirectional"))
      (node (ref "IC1") (pin "3") (pinfunction "GND_3") (pintype "bidirectional"))
      (node (ref "IC2") (pin "1") (pinfunction "GND_1") (pintype "bidirectional"))
      (node (ref "IC3") (pin "1") (pinfunction "GND_1") (pintype "bidirectional"))
      (node (ref "JACK") (pin "1") (pinfunction "GND_1") (pintype "bidirectional"))
      (node (ref "OS1") (pin "E") (pinfunction "EMITTER_E") (pintype "passive"))
      (node (ref "OS2") (pin "E") (pinfunction "EMITTER_E") (pintype "passive"))
      (node (ref "OS3") (pin "E") (pinfunction "EMITTER_E") (pintype "passive"))
      (node (ref "OS4") (pin "E") (pinfunction "EMITTER_E") (pintype "passive"))
      (node (ref "OS5") (pin "E") (pinfunction "EMITTER_E") (pintype "passive"))
      (node (ref "OS6") (pin "E") (pinfunction "EMITTER_E") (pintype "passive"))
      (node (ref "OS7") (pin "E") (pinfunction "EMITTER_E") (pintype "passive"))
      (node (ref "OS8") (pin "E") (pinfunction "EMITTER_E") (pintype "passive"))
      (node (ref "P1") (pin "3") (pinfunction "GND_3") (pintype "bidirectional"))
      (node (ref "PROGRAM") (pin "1") (pinfunction "1_1") (pintype "passive"))
      (node (ref "PWR") (pin "2") (pinfunction "2_2") (pintype "passive"))
      (node (ref "R24") (pin "1") (pinfunction "1_1") (pintype "passive"))
      (node (ref "R28") (pin "1") (pinfunction "1_1") (pintype "passive"))
      (node (ref "R39") (pin "2") (pinfunction "2_2") (pintype "passive"))
      (node (ref "R41") (pin "2") (pinfunction "2_2") (pintype "passive"))
      (node (ref "U$1") (pin "1") (pinfunction "GND_1") (pintype "bidirectional"))
      (node (ref "U$14") (pin "-") (pinfunction "-_-") (pintype "passive"))
      (node (ref "U$18") (pin "A1") (pinfunction "P$1_A1") (pintype "bidirectional"))
      (node (ref "U$18") (pin "A2") (pinfunction "P$1_A2") (pintype "bidirectional"))
      (node (ref "U$19") (pin "A1") (pinfunction "P$1_A1") (pintype "bidirectional"))
      (node (ref "U$19") (pin "A2") (pinfunction "P$1_A2") (pintype "bidirectional"))
      (node (ref "U$2") (pin "1") (pinfunction "GND_1") (pintype "passive"))
      (node (ref "U$20") (pin "A1") (pinfunction "P$1_A1") (pintype "bidirectional"))
      (node (ref "U$20") (pin "A2") (pinfunction "P$1_A2") (pintype "bidirectional"))
      (node (ref "U$21") (pin "A1") (pinfunction "P$1_A1") (pintype "bidirectional"))
      (node (ref "U$21") (pin "A2") (pinfunction "P$1_A2") (pintype "bidirectional"))
      (node (ref "U$22") (pin "A1") (pinfunction "P$1_A1") (pintype "bidirectional"))
      (node (ref "U$22") (pin "A2") (pinfunction "P$1_A2") (pintype "bidirectional"))
      (node (ref "U$23") (pin "A1") (pinfunction "P$1_A1") (pintype "bidirectional"))
      (node (ref "U$23") (pin "A2") (pinfunction "P$1_A2") (pintype "bidirectional"))
      (node (ref "U$24") (pin "GND") (pinfunction "GND_GND") (pintype "bidirectional"))
      (node (ref "U$28") (pin "2") (pinfunction "E_2") (pintype "passive"))
      (node (ref "U$29") (pin "2") (pinfunction "E_2") (pintype "passive"))
      (node (ref "U$9") (pin "-") (pinfunction "-_-") (pintype "passive"))
      (node (ref "U1") (pin "6") (pinfunction "INH_6") (pintype "input"))
      (node (ref "U1") (pin "7") (pinfunction "VSS_7") (pintype "power_in"))
      (node (ref "U1") (pin "8") (pinfunction "VEE_8") (pintype "power_in"))
      (node (ref "U2") (pin "6") (pinfunction "INH_6") (pintype "input"))
      (node (ref "U2") (pin "7") (pinfunction "VSS_7") (pintype "power_in"))
      (node (ref "U2") (pin "8") (pinfunction "VEE_8") (pintype "power_in"))
      (node (ref "U3") (pin "1") (pinfunction "SHDN_1") (pintype "passive"))
      (node (ref "U3") (pin "7") (pinfunction "V-_7") (pintype "power_in"))
      (node (ref "UC1") (pin "23") (pinfunction "VSS_1_23") (pintype "power_in"))
      (node (ref "UC1") (pin "35") (pinfunction "VSS_2_35") (pintype "power_in"))
      (node (ref "UC1") (pin "47") (pinfunction "VSS_3_47") (pintype "power_in"))
      (node (ref "UC1") (pin "8") (pinfunction "VSS_A_8") (pintype "power_in"))
      (node (ref "X1") (pin "GND") (pinfunction "GND_GND") (pintype "bidirectional"))
    )
    (net (code "53") (name "Net-(BUT-1)") (class "Default")
      (node (ref "BUT") (pin "P$1") (pinfunction "1_P$1") (pintype "passive"))
      (node (ref "BUT") (pin "P$3") (pinfunction "3_P$3") (pintype "passive"))
      (node (ref "R38") (pin "2") (pinfunction "2_2") (pintype "passive"))
    )
    (net (code "54") (name "Net-(BUT-2)") (class "Default")
      (node (ref "BUT") (pin "P$2") (pinfunction "2_P$2") (pintype "passive"))
      (node (ref "BUT") (pin "P$4") (pinfunction "4_P$4") (pintype "passive"))
      (node (ref "R39") (pin "1") (pinfunction "1_1") (pintype "passive"))
      (node (ref "UC1") (pin "37") (pinfunction "PA14/JTCK/SWCLK_37") (pintype "bidirectional"))
      (node (ref "UC1") (pin "44") (pinfunction "BOOT0_44") (pintype "input"))
    )
    (net (code "55") (name "Net-(C14-+)") (class "Default")
      (node (ref "C14") (pin "A") (pinfunction "+_A") (pintype "passive"))
      (node (ref "D2") (pin "1") (pinfunction "C_1") (pintype "passive"))
      (node (ref "D3") (pin "1") (pinfunction "C_1") (pintype "passive"))
      (node (ref "IC2") (pin "3") (pinfunction "VIN_3") (pintype "bidirectional"))
      (node (ref "IC3") (pin "3") (pinfunction "VIN_3") (pintype "bidirectional"))
    )
    (net (code "56") (name "Net-(C17-Pad2)") (class "Default")
      (node (ref "C17") (pin "2") (pinfunction "2_2") (pintype "passive"))
      (node (ref "R22") (pin "1") (pinfunction "1_1") (pintype "passive"))
    )
    (net (code "57") (name "Net-(D1-PadA)") (class "Default")
      (node (ref "D1") (pin "A") (pinfunction "A_A") (pintype "passive"))
      (node (ref "R30") (pin "2") (pinfunction "2_2") (pintype "passive"))
    )
    (net (code "58") (name "Net-(D4-PadA)") (class "Default")
      (node (ref "D4") (pin "A") (pinfunction "A_A") (pintype "passive"))
      (node (ref "R26") (pin "2") (pinfunction "2_2") (pintype "passive"))
    )
    (net (code "59") (name "Net-(D5-PadA)") (class "Default")
      (node (ref "D5") (pin "A") (pinfunction "A_A") (pintype "passive"))
      (node (ref "R27") (pin "2") (pinfunction "2_2") (pintype "passive"))
    )
    (net (code "60") (name "Net-(IC1-CHRG)") (class "Default")
      (node (ref "D4") (pin "C") (pinfunction "C_C") (pintype "passive"))
      (node (ref "IC1") (pin "7") (pinfunction "CHRG_7") (pintype "bidirectional"))
    )
    (net (code "61") (name "Net-(IC1-PROG)") (class "Default")
      (node (ref "IC1") (pin "2") (pinfunction "PROG_2") (pintype "bidirectional"))
      (node (ref "R24") (pin "2") (pinfunction "2_2") (pintype "passive"))
    )
    (net (code "62") (name "Net-(IC1-STDBY)") (class "Default")
      (node (ref "D5") (pin "C") (pinfunction "C_C") (pintype "passive"))
      (node (ref "IC1") (pin "6") (pinfunction "STDBY_6") (pintype "bidirectional"))
    )
    (net (code "63") (name "Net-(JACK-IN_A)") (class "Default")
      (node (ref "JACK") (pin "2") (pinfunction "IN_A_2") (pintype "bidirectional"))
      (node (ref "JACK") (pin "5") (pinfunction "IN_B_5") (pintype "bidirectional"))
      (node (ref "R19") (pin "2") (pinfunction "2_2") (pintype "passive"))
    )
    (net (code "64") (name "Net-(OS1-ANODE)") (class "Default")
      (node (ref "OS1") (pin "A") (pinfunction "ANODE_A") (pintype "passive"))
      (node (ref "R3") (pin "2") (pinfunction "2_2") (pintype "passive"))
    )
    (net (code "65") (name "Net-(OS2-ANODE)") (class "Default")
      (node (ref "OS2") (pin "A") (pinfunction "ANODE_A") (pintype "passive"))
      (node (ref "R7") (pin "1") (pinfunction "1_1") (pintype "passive"))
    )
    (net (code "66") (name "Net-(OS3-ANODE)") (class "Default")
      (node (ref "OS3") (pin "A") (pinfunction "ANODE_A") (pintype "passive"))
      (node (ref "R10") (pin "1") (pinfunction "1_1") (pintype "passive"))
    )
    (net (code "67") (name "Net-(OS4-ANODE)") (class "Default")
      (node (ref "OS4") (pin "A") (pinfunction "ANODE_A") (pintype "passive"))
      (node (ref "R11") (pin "1") (pinfunction "1_1") (pintype "passive"))
    )
    (net (code "68") (name "Net-(OS5-ANODE)") (class "Default")
      (node (ref "OS5") (pin "A") (pinfunction "ANODE_A") (pintype "passive"))
      (node (ref "R5") (pin "2") (pinfunction "2_2") (pintype "passive"))
    )
    (net (code "69") (name "Net-(OS6-ANODE)") (class "Default")
      (node (ref "OS6") (pin "A") (pinfunction "ANODE_A") (pintype "passive"))
      (node (ref "R8") (pin "1") (pinfunction "1_1") (pintype "passive"))
    )
    (net (code "70") (name "Net-(OS7-ANODE)") (class "Default")
      (node (ref "OS7") (pin "A") (pinfunction "ANODE_A") (pintype "passive"))
      (node (ref "R9") (pin "1") (pinfunction "1_1") (pintype "passive"))
    )
    (net (code "71") (name "Net-(OS8-ANODE)") (class "Default")
      (node (ref "OS8") (pin "A") (pinfunction "ANODE_A") (pintype "passive"))
      (node (ref "R12") (pin "1") (pinfunction "1_1") (pintype "passive"))
    )
    (net (code "72") (name "Net-(R31-Pad1)") (class "Default")
      (node (ref "R31") (pin "1") (pinfunction "1_1") (pintype "passive"))
      (node (ref "X1") (pin "D-") (pinfunction "D-_D-") (pintype "bidirectional"))
    )
    (net (code "73") (name "Net-(R32-Pad1)") (class "Default")
      (node (ref "R32") (pin "1") (pinfunction "1_1") (pintype "passive"))
      (node (ref "X1") (pin "D+") (pinfunction "D+_D+") (pintype "bidirectional"))
    )
    (net (code "74") (name "Net-(RESET-1)") (class "Default")
      (node (ref "R41") (pin "1") (pinfunction "1_1") (pintype "passive"))
      (node (ref "RESET") (pin "P$1") (pinfunction "1_P$1") (pintype "passive"))
      (node (ref "RESET") (pin "P$3") (pinfunction "3_P$3") (pintype "passive"))
    )
    (net (code "75") (name "Net-(U$1-C+)") (class "Default")
      (node (ref "C15") (pin "2") (pinfunction "2_2") (pintype "passive"))
      (node (ref "U$1") (pin "5") (pinfunction "C+_5") (pintype "bidirectional"))
    )
    (net (code "76") (name "Net-(U$1-C-)") (class "Default")
      (node (ref "C15") (pin "1") (pinfunction "1_1") (pintype "passive"))
      (node (ref "U$1") (pin "3") (pinfunction "C-_3") (pintype "bidirectional"))
    )
    (net (code "77") (name "Net-(U$1-VOUT)") (class "Default")
      (node (ref "C16") (pin "2") (pinfunction "2_2") (pintype "passive"))
      (node (ref "U$1") (pin "2") (pinfunction "VOUT_2") (pintype "bidirectional"))
      (node (ref "U$2") (pin "3") (pinfunction "VIN_3") (pintype "input"))
    )
    (net (code "78") (name "Net-(U$28-B)") (class "Default")
      (node (ref "R1") (pin "2") (pinfunction "2_2") (pintype "passive"))
      (node (ref "U$28") (pin "1") (pinfunction "B_1") (pintype "passive"))
    )
    (net (code "79") (name "Net-(U$29-B)") (class "Default")
      (node (ref "R2") (pin "2") (pinfunction "2_2") (pintype "passive"))
      (node (ref "U$29") (pin "1") (pinfunction "B_1") (pintype "passive"))
    )
    (net (code "80") (name "Net-(U3-BYPASS)") (class "Default")
      (node (ref "C1") (pin "2") (pinfunction "2_2") (pintype "passive"))
      (node (ref "U3") (pin "2") (pinfunction "BYPASS_2") (pintype "passive"))
      (node (ref "U3") (pin "3") (pinfunction "IN+_3") (pintype "input"))
    )
    (net (code "81") (name "Net-(U3-IN-)") (class "Default")
      (node (ref "R21") (pin "1") (pinfunction "1_1") (pintype "passive"))
      (node (ref "R22") (pin "2") (pinfunction "2_2") (pintype "passive"))
      (node (ref "U3") (pin "4") (pinfunction "IN-_4") (pintype "input"))
    )
    (net (code "82") (name "Net-(U3-VOUTB)") (class "Default")
      (node (ref "SPEAKER") (pin "2") (pinfunction "2_2") (pintype "passive"))
      (node (ref "U3") (pin "8") (pinfunction "VOUTB_8") (pintype "output"))
    )
    (net (code "83") (name "Net-(UC1-PA13{slash}JTMS{slash}SWDIO)") (class "Default")
      (node (ref "R30") (pin "1") (pinfunction "1_1") (pintype "passive"))
      (node (ref "UC1") (pin "34") (pinfunction "PA13/JTMS/SWDIO_34") (pintype "bidirectional"))
    )
    (net (code "84") (name "unconnected-(DAC-~{SHDN}-Pad6)") (class "Default")
      (node (ref "DAC") (pin "6") (pinfunction "~{SHDN}_6") (pintype "input"))
    )
    (net (code "85") (name "unconnected-(U1-7-Pad4)") (class "Default")
      (node (ref "U1") (pin "4") (pinfunction "7_4") (pintype "bidirectional"))
    )
    (net (code "86") (name "unconnected-(U2-7-Pad4)") (class "Default")
      (node (ref "U2") (pin "4") (pinfunction "7_4") (pintype "bidirectional"))
    )
    (net (code "87") (name "unconnected-(UC1-PA3{slash}USART2_RX{slash}ADC12_IN3{slash}TIM2_CH4-Pad13)") (class "Default")
      (node (ref "UC1") (pin "13") (pinfunction "PA3/USART2_RX/ADC12_IN3/TIM2_CH4_13") (pintype "bidirectional"))
    )
    (net (code "88") (name "unconnected-(UC1-PA4{slash}SPI1_NSS{slash}USART2_CK{slash}ADC12_IN4-Pad14)") (class "Default")
      (node (ref "UC1") (pin "14") (pinfunction "PA4/SPI1_NSS/USART2_CK/ADC12_IN4_14") (pintype "bidirectional"))
    )
    (net (code "89") (name "unconnected-(UC1-PA5{slash}SPI1_SCK{slash}ADC12_IN5-Pad15)") (class "Default")
      (node (ref "UC1") (pin "15") (pinfunction "PA5/SPI1_SCK/ADC12_IN5_15") (pintype "bidirectional"))
    )
    (net (code "90") (name "unconnected-(UC1-PA6{slash}SPI1_MISO{slash}ADC12_IN6{slash}TIM3_CH1-Pad16)") (class "Default")
      (node (ref "UC1") (pin "16") (pinfunction "PA6/SPI1_MISO/ADC12_IN6/TIM3_CH1_16") (pintype "bidirectional"))
    )
    (net (code "91") (name "unconnected-(UC1-PA7{slash}SPI1_MOSI{slash}ADC12_IN7{slash}TIM3_CH2-Pad17)") (class "Default")
      (node (ref "UC1") (pin "17") (pinfunction "PA7/SPI1_MOSI/ADC12_IN7/TIM3_CH2_17") (pintype "bidirectional"))
    )
    (net (code "92") (name "unconnected-(UC1-PA15{slash}JTDI-Pad38)") (class "Default")
      (node (ref "UC1") (pin "38") (pinfunction "PA15/JTDI_38") (pintype "bidirectional"))
    )
    (net (code "93") (name "unconnected-(UC1-PB0{slash}ADC12_IN8{slash}TIM3_CH3-Pad18)") (class "Default")
      (node (ref "UC1") (pin "18") (pinfunction "PB0/ADC12_IN8/TIM3_CH3_18") (pintype "bidirectional"))
    )
    (net (code "94") (name "unconnected-(UC1-PB1{slash}ADC12_IN9{slash}TIM3_CH4-Pad19)") (class "Default")
      (node (ref "UC1") (pin "19") (pinfunction "PB1/ADC12_IN9/TIM3_CH4_19") (pintype "bidirectional"))
    )
    (net (code "95") (name "unconnected-(UC1-PB3{slash}JTDO-Pad39)") (class "Default")
      (node (ref "UC1") (pin "39") (pinfunction "PB3/JTDO_39") (pintype "bidirectional"))
    )
    (net (code "96") (name "unconnected-(UC1-PB4{slash}NJTRST-Pad40)") (class "Default")
      (node (ref "UC1") (pin "40") (pinfunction "PB4/NJTRST_40") (pintype "bidirectional"))
    )
    (net (code "97") (name "unconnected-(UC1-PB14{slash}SPI2_MISO{slash}USART3_RTS{slash}TIM1_CH2N-Pad27)") (class "Default")
      (node (ref "UC1") (pin "27") (pinfunction "PB14/SPI2_MISO/USART3_RTS/TIM1_CH2N_27") (pintype "input"))
    )
    (net (code "98") (name "unconnected-(UC1-PC13-TAMPER-RTC-Pad2)") (class "Default")
      (node (ref "UC1") (pin "2") (pinfunction "PC13-TAMPER-RTC_2") (pintype "input"))
    )
  )
)
